# Top_Level.net
KiCad netlist of a schematic drawn in Altium Designer
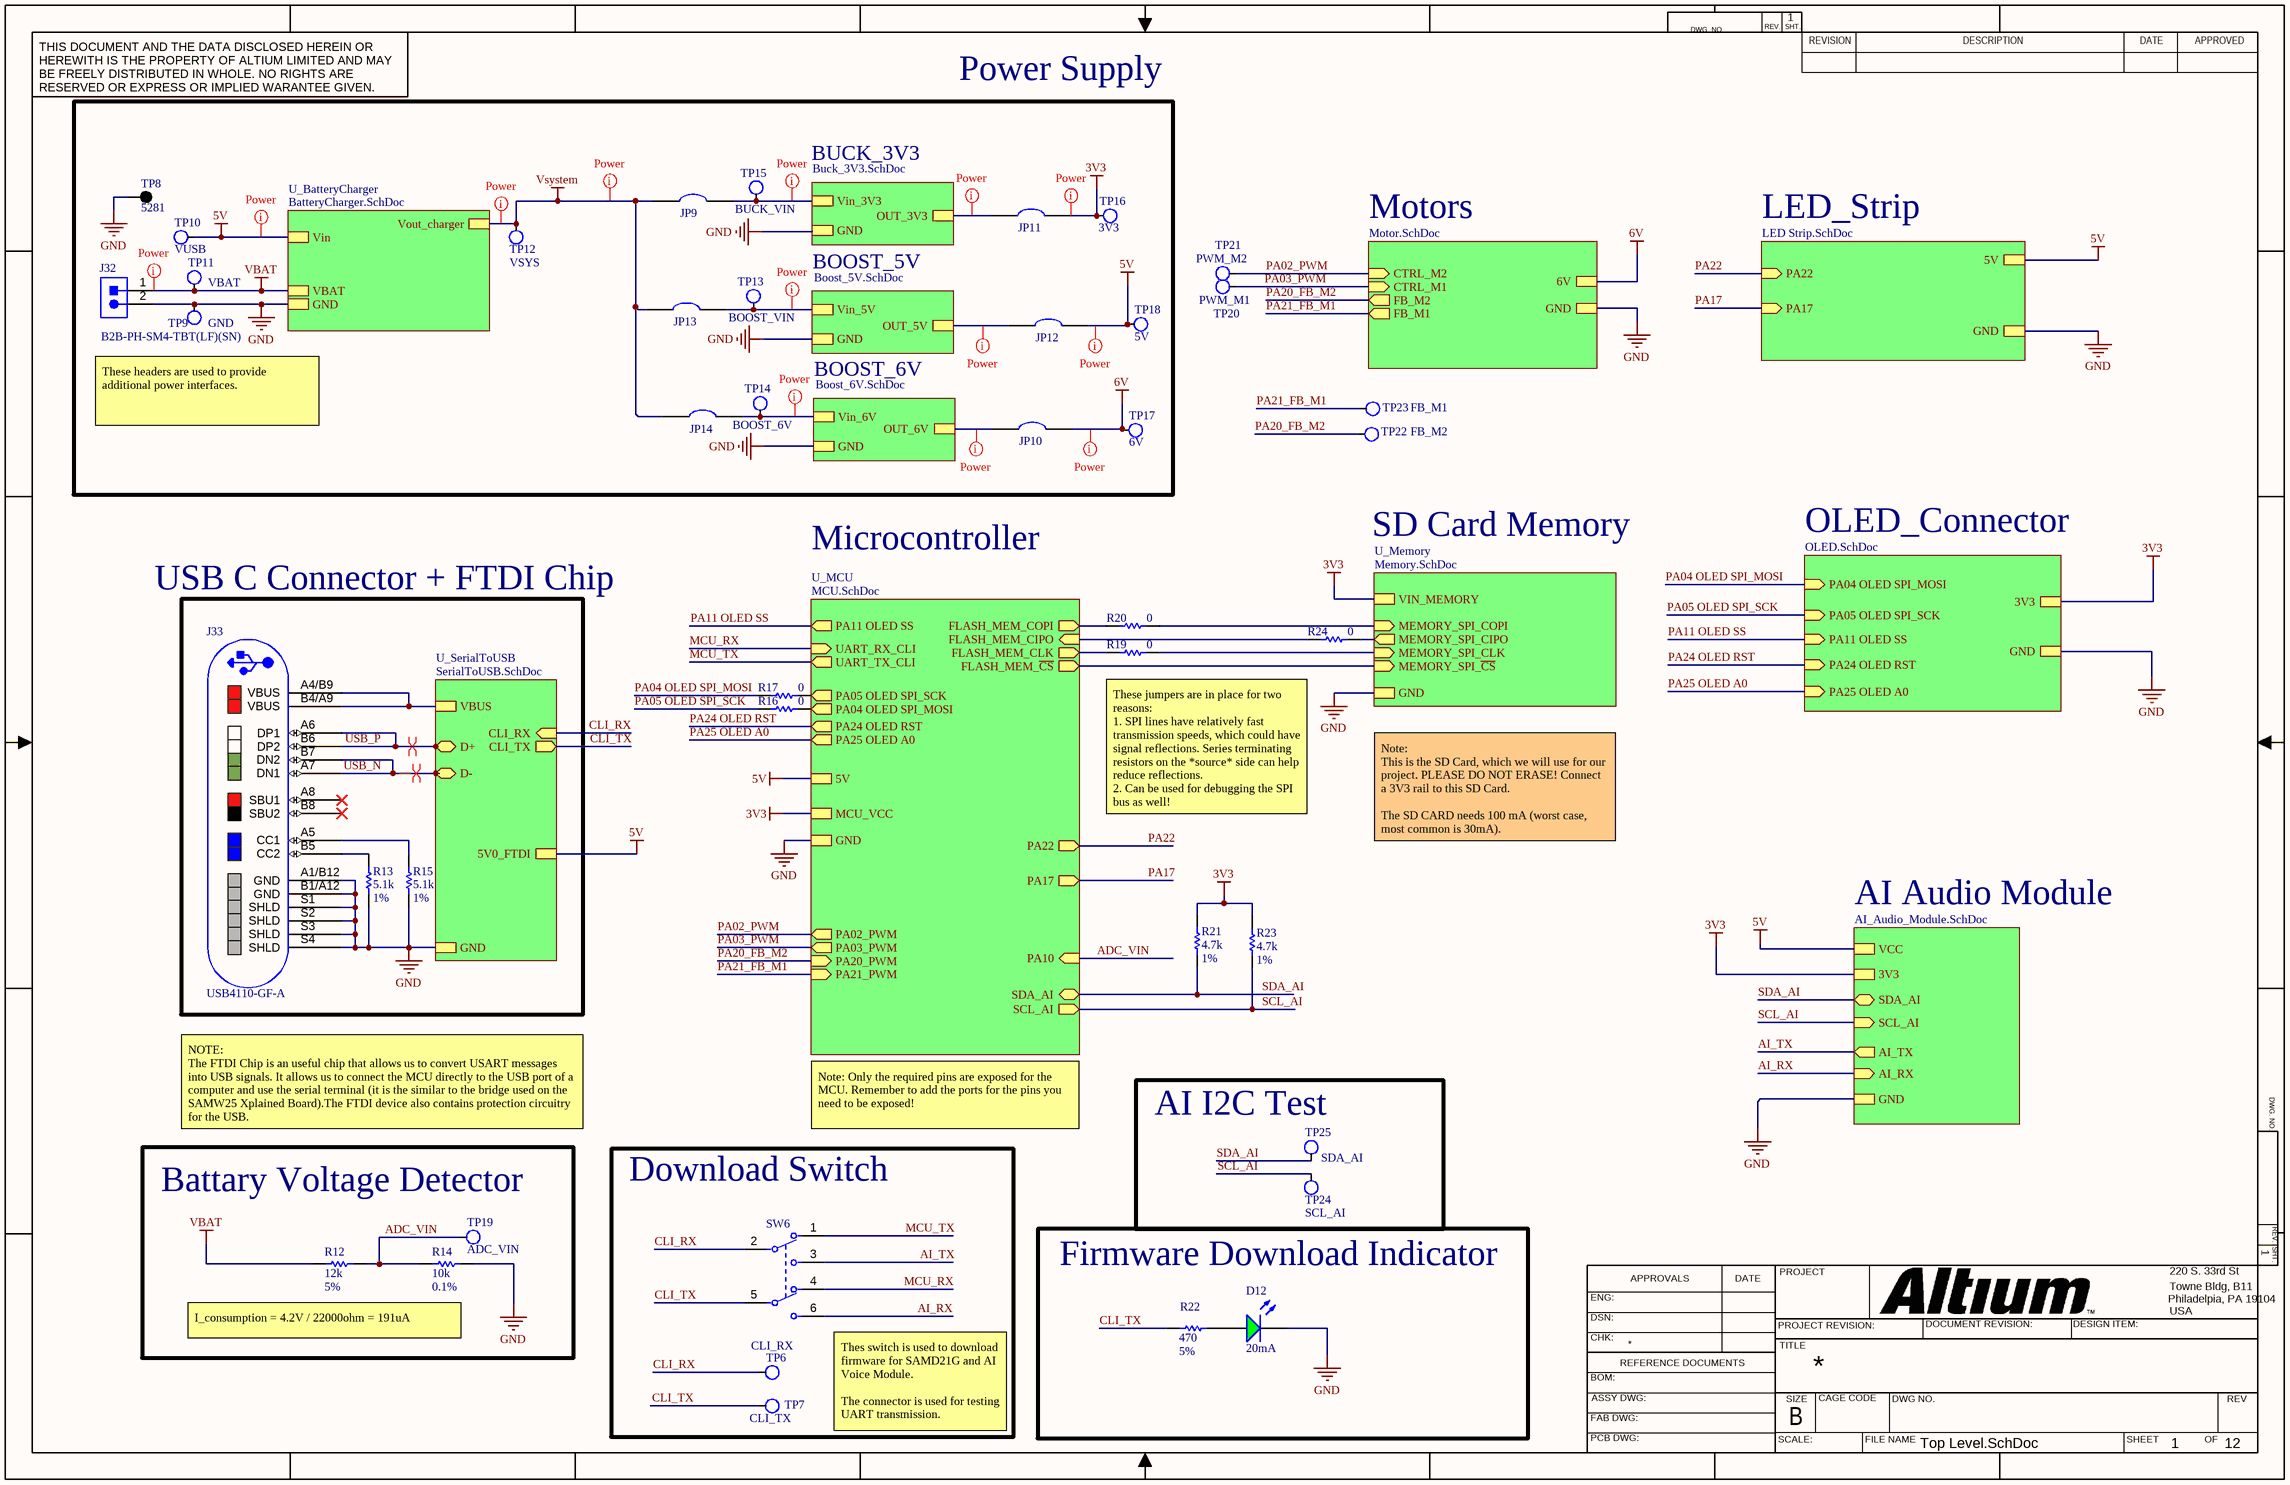
[diagram p0: Top Level.SchDoc]

(export (version "E")
  (design (tool "Eeschema 10.0.6"))
  (components
    (comp (ref "D12")
      (value "LSM0805452V")
      (footprint "LED_0805")
      (description "Single Color LED, Green, 0805")
      (fields (field (name "CURRENT") "20mA"))
      (libsource (lib "University of Pennsylvania (ESE)") (part "LED-GREEN-AK-2"))
    )
    (comp (ref "J32")
      (value "B2B-PH-SM4-TBT(LF)(SN)")
      (footprint "FP-B2B-PH-SM4-TBT_LF_SN-MFG")
      (libsource (lib "University of Pennsylvania (ESE)") (part "Header 1X2"))
    )
    (comp (ref "J33")
      (value "USB4110-GF-A")
      (footprint "FP-USB4110-GF-A-MFG")
      (libsource (lib "University of Pennsylvania (ESE)") (part "USB4110-GF-A"))
    )
    (comp (ref "JP9")
      (value "0603 link")
      (footprint "0603_JP_RES")
      (description "0O link, SMD, 0603, Solder Bridge Option")
      (fields (field (name "MANUFACTURER") "Generic") (field (name "SOURCE") "Shunts and Jumpers.SchLib"))
      (libsource (lib "University of Pennsylvania (ESE)") (part "CMP-ROOT-0007-1"))
    )
    (comp (ref "JP10")
      (value "0603 link")
      (footprint "0603_JP_RES")
      (description "0O link, SMD, 0603, Solder Bridge Option")
      (fields (field (name "MANUFACTURER") "Generic") (field (name "SOURCE") "Shunts and Jumpers.SchLib"))
      (libsource (lib "University of Pennsylvania (ESE)") (part "CMP-ROOT-0007-1"))
    )
    (comp (ref "JP11")
      (value "0603 link")
      (footprint "0603_JP_RES")
      (description "0O link, SMD, 0603, Solder Bridge Option")
      (fields (field (name "MANUFACTURER") "Generic") (field (name "SOURCE") "Shunts and Jumpers.SchLib"))
      (libsource (lib "University of Pennsylvania (ESE)") (part "CMP-ROOT-0007-1"))
    )
    (comp (ref "JP12")
      (value "0603 link")
      (footprint "0603_JP_RES")
      (description "0O link, SMD, 0603, Solder Bridge Option")
      (fields (field (name "MANUFACTURER") "Generic") (field (name "SOURCE") "Shunts and Jumpers.SchLib"))
      (libsource (lib "University of Pennsylvania (ESE)") (part "CMP-ROOT-0007-1"))
    )
    (comp (ref "JP13")
      (value "0603 link")
      (footprint "0603_JP_RES")
      (description "0O link, SMD, 0603, Solder Bridge Option")
      (fields (field (name "MANUFACTURER") "Generic") (field (name "SOURCE") "Shunts and Jumpers.SchLib"))
      (libsource (lib "University of Pennsylvania (ESE)") (part "CMP-ROOT-0007-1"))
    )
    (comp (ref "JP14")
      (value "0603 link")
      (footprint "0603_JP_RES")
      (description "0O link, SMD, 0603, Solder Bridge Option")
      (fields (field (name "MANUFACTURER") "Generic") (field (name "SOURCE") "Shunts and Jumpers.SchLib"))
      (libsource (lib "University of Pennsylvania (ESE)") (part "CMP-ROOT-0007-1"))
    )
    (comp (ref "R12")
      (value "12k")
      (footprint "0603_RES")
      (description "Resistor Surface Mount, 12K Ohms, 0603 Footprint, 5% Tolerance 0.1W")
      (fields
        (field (name "TOLERANCE") "5%")
        (field (name "MANUFACTURER") "Various")
        (field (name "Comment") "RES 0603 12K 5%")
      )
      (libsource (lib "University of Pennsylvania (ESE)") (part "res"))
    )
    (comp (ref "R13")
      (value "5.1k")
      (footprint "0603_RES")
      (description "Resistor Surface Mount, 5.1K Ohms, 0603 Footprint, 1% Tolerance 0.1W")
      (fields
        (field (name "TOLERANCE") "1%")
        (field (name "MANUFACTURER") "Various")
        (field (name "Comment") "RES 0603 5.1K 1%")
      )
      (libsource (lib "University of Pennsylvania (ESE)") (part "res"))
    )
    (comp (ref "R14")
      (value "10k")
      (footprint "0603_RES")
      (description "Resistor Surface Mount, 10K Ohms, 0603 Footprint, 0.1% Tolerance 0.1W")
      (fields
        (field (name "TOLERANCE") "0.1%")
        (field (name "MANUFACTURER") "Various")
        (field (name "Comment") "RES 0603 10K 0.1%")
      )
      (libsource (lib "University of Pennsylvania (ESE)") (part "res"))
    )
    (comp (ref "R15")
      (value "5.1k")
      (footprint "0603_RES")
      (description "Resistor Surface Mount, 5.1K Ohms, 0603 Footprint, 1% Tolerance 0.1W")
      (fields
        (field (name "TOLERANCE") "1%")
        (field (name "MANUFACTURER") "Various")
        (field (name "Comment") "RES 0603 5.1K 1%")
      )
      (libsource (lib "University of Pennsylvania (ESE)") (part "res"))
    )
    (comp (ref "R16")
      (value "0")
      (footprint "0603_RES")
      (description "Resistor Surface Mount, 0 Ohms, 0603 Footprint, 5% Tolerance 0.1W")
      (fields (field (name "TOLERANCE") "5%") (field (name "JLCPCB PART #") "C21189"))
      (libsource (lib "University of Pennsylvania (ESE)") (part "res"))
    )
    (comp (ref "R17")
      (value "0")
      (footprint "0603_RES")
      (description "Resistor Surface Mount, 0 Ohms, 0603 Footprint, 5% Tolerance 0.1W")
      (fields (field (name "TOLERANCE") "5%") (field (name "JLCPCB PART #") "C21189"))
      (libsource (lib "University of Pennsylvania (ESE)") (part "res"))
    )
    (comp (ref "R19")
      (value "0")
      (footprint "0603_RES")
      (description "Resistor Surface Mount, 0 Ohms, 0603 Footprint, 5% Tolerance 0.1W")
      (fields (field (name "TOLERANCE") "5%") (field (name "JLCPCB PART #") "C21189"))
      (libsource (lib "University of Pennsylvania (ESE)") (part "res"))
    )
    (comp (ref "R20")
      (value "0")
      (footprint "0603_RES")
      (description "Resistor Surface Mount, 0 Ohms, 0603 Footprint, 5% Tolerance 0.1W")
      (fields (field (name "TOLERANCE") "5%") (field (name "JLCPCB PART #") "C21189"))
      (libsource (lib "University of Pennsylvania (ESE)") (part "res"))
    )
    (comp (ref "R21")
      (value "4.7k")
      (footprint "0603_RES")
      (description "Resistor Surface Mount, 4.7K Ohms, 0603 Footprint, 1% Tolerance 0.1W")
      (fields
        (field (name "TOLERANCE") "1%")
        (field (name "MANUFACTURER") "Various")
        (field (name "Comment") "RES 0603 4.7K 1%")
      )
      (libsource (lib "University of Pennsylvania (ESE)") (part "res"))
    )
    (comp (ref "R22")
      (value "470")
      (footprint "0805_RES")
      (description "Resistor Surface Mount, 470 Ohms, 0805 Footprint, 5% Tolerance 0.125W")
      (fields
        (field (name "TOLERANCE") "5%")
        (field (name "MANUFACTURER") "Various")
        (field (name "Comment") "RES 0805 470 5%")
      )
      (libsource (lib "University of Pennsylvania (ESE)") (part "res"))
    )
    (comp (ref "R23")
      (value "4.7k")
      (footprint "0603_RES")
      (description "Resistor Surface Mount, 4.7K Ohms, 0603 Footprint, 1% Tolerance 0.1W")
      (fields
        (field (name "TOLERANCE") "1%")
        (field (name "MANUFACTURER") "Various")
        (field (name "Comment") "RES 0603 4.7K 1%")
      )
      (libsource (lib "University of Pennsylvania (ESE)") (part "res"))
    )
    (comp (ref "R24")
      (value "0")
      (footprint "0603_RES")
      (description "Resistor Surface Mount, 0 Ohms, 0603 Footprint, 5% Tolerance 0.1W")
      (fields (field (name "TOLERANCE") "5%") (field (name "JLCPCB PART #") "C21189"))
      (libsource (lib "University of Pennsylvania (ESE)") (part "res"))
    )
    (comp (ref "SW6")
      (value "JS202011JCQN")
      (footprint "FP-JS202011JCQN-MFG")
      (description "Slide Switch, 2 Positions, DPDT, Latched, 0.3A, 6VDC, Solder Terminal, Surface Mount-straight")
      (libsource (lib "University of Pennsylvania (ESE)") (part "DPDT"))
    )
    (comp (ref "TP6")
      (value "Testpad")
      (footprint "Keystone 5000 Series")
      (description "Test Pad/Point (Testpoint, Testpad), for probing")
      (fields (field (name "NETNAME") "CLI_RX"))
      (libsource (lib "University of Pennsylvania (ESE)") (part "Test Pad"))
    )
    (comp (ref "TP7")
      (value "Testpad")
      (footprint "Keystone 5000 Series")
      (description "Test Pad/Point (Testpoint, Testpad), for probing")
      (fields (field (name "NETNAME") "CLI_TX"))
      (libsource (lib "University of Pennsylvania (ESE)") (part "Test Pad"))
    )
    (comp (ref "TP8")
      (value "5281")
      (footprint "KSTN-5011_V")
      (description "Circuit Board Hardware - PCB TEST POINT BLACK MULTIPURPOSE 5011 5281")
      (libsource (lib "University of Pennsylvania (ESE)") (part "TESTPOINT_BLACK"))
    )
    (comp (ref "TP9")
      (value "Testpad")
      (footprint "Testpad-HeaderPin")
      (description "Test Pad/Point (Testpoint, Testpad), for probing")
      (fields (field (name "NETNAME") "GND"))
      (libsource (lib "University of Pennsylvania (ESE)") (part "Test Pad"))
    )
    (comp (ref "TP10")
      (value "Testpad")
      (footprint "Keystone 5000 Series")
      (description "Test Pad/Point (Testpoint, Testpad), for probing")
      (fields (field (name "NETNAME") "VUSB"))
      (libsource (lib "University of Pennsylvania (ESE)") (part "Test Pad"))
    )
    (comp (ref "TP11")
      (value "Testpad")
      (footprint "Keystone 5000 Series")
      (description "Test Pad/Point (Testpoint, Testpad), for probing")
      (fields (field (name "NETNAME") "VBAT"))
      (libsource (lib "University of Pennsylvania (ESE)") (part "Test Pad"))
    )
    (comp (ref "TP12")
      (value "Testpad")
      (footprint "Keystone 5000 Series")
      (description "Test Pad/Point (Testpoint, Testpad), for probing")
      (fields (field (name "NETNAME") "VSYS"))
      (libsource (lib "University of Pennsylvania (ESE)") (part "Test Pad"))
    )
    (comp (ref "TP13")
      (value "Testpad")
      (footprint "Keystone 5000 Series")
      (description "Test Pad/Point (Testpoint, Testpad), for probing")
      (fields (field (name "NETNAME") "BOOST_VIN"))
      (libsource (lib "University of Pennsylvania (ESE)") (part "Test Pad"))
    )
    (comp (ref "TP14")
      (value "Testpad")
      (footprint "Keystone 5000 Series")
      (description "Test Pad/Point (Testpoint, Testpad), for probing")
      (fields (field (name "NETNAME") "BOOST_6V"))
      (libsource (lib "University of Pennsylvania (ESE)") (part "Test Pad"))
    )
    (comp (ref "TP15")
      (value "Testpad")
      (footprint "Keystone 5000 Series")
      (description "Test Pad/Point (Testpoint, Testpad), for probing")
      (fields (field (name "NETNAME") "BUCK_VIN"))
      (libsource (lib "University of Pennsylvania (ESE)") (part "Test Pad"))
    )
    (comp (ref "TP16")
      (value "Testpad")
      (footprint "Keystone 5000 Series")
      (description "Test Pad/Point (Testpoint, Testpad), for probing")
      (fields (field (name "NETNAME") "3V3"))
      (libsource (lib "University of Pennsylvania (ESE)") (part "Test Pad"))
    )
    (comp (ref "TP17")
      (value "Testpad")
      (footprint "Keystone 5000 Series")
      (description "Test Pad/Point (Testpoint, Testpad), for probing")
      (fields (field (name "NETNAME") "6V"))
      (libsource (lib "University of Pennsylvania (ESE)") (part "Test Pad"))
    )
    (comp (ref "TP18")
      (value "Testpad")
      (footprint "Keystone 5000 Series")
      (description "Test Pad/Point (Testpoint, Testpad), for probing")
      (fields (field (name "NETNAME") "5V"))
      (libsource (lib "University of Pennsylvania (ESE)") (part "Test Pad"))
    )
    (comp (ref "TP19")
      (value "Testpad")
      (footprint "Keystone 5000 Series")
      (description "Test Pad/Point (Testpoint, Testpad), for probing")
      (fields (field (name "NETNAME") "ADC_VIN"))
      (libsource (lib "University of Pennsylvania (ESE)") (part "Test Pad"))
    )
    (comp (ref "TP20")
      (value "Testpad")
      (footprint "Keystone 5000 Series")
      (description "Test Pad/Point (Testpoint, Testpad), for probing")
      (fields (field (name "NETNAME") "PWM_M1"))
      (libsource (lib "University of Pennsylvania (ESE)") (part "Test Pad"))
    )
    (comp (ref "TP21")
      (value "Testpad")
      (footprint "Keystone 5000 Series")
      (description "Test Pad/Point (Testpoint, Testpad), for probing")
      (fields (field (name "NETNAME") "PWM_M2"))
      (libsource (lib "University of Pennsylvania (ESE)") (part "Test Pad"))
    )
    (comp (ref "TP22")
      (value "Testpad")
      (footprint "Keystone 5000 Series")
      (description "Test Pad/Point (Testpoint, Testpad), for probing")
      (fields (field (name "NETNAME") "FB_M2"))
      (libsource (lib "University of Pennsylvania (ESE)") (part "Test Pad"))
    )
    (comp (ref "TP23")
      (value "Testpad")
      (footprint "Keystone 5000 Series")
      (description "Test Pad/Point (Testpoint, Testpad), for probing")
      (fields (field (name "NETNAME") "FB_M1"))
      (libsource (lib "University of Pennsylvania (ESE)") (part "Test Pad"))
    )
    (comp (ref "TP24")
      (value "Testpad")
      (footprint "Keystone 5000 Series")
      (description "Test Pad/Point (Testpoint, Testpad), for probing")
      (fields (field (name "NETNAME") "SCL_AI"))
      (libsource (lib "University of Pennsylvania (ESE)") (part "Test Pad"))
    )
    (comp (ref "TP25")
      (value "Testpad")
      (footprint "Keystone 5000 Series")
      (description "Test Pad/Point (Testpoint, Testpad), for probing")
      (fields (field (name "NETNAME") "SDA_AI"))
      (libsource (lib "University of Pennsylvania (ESE)") (part "Test Pad"))
    )
  )
  (nets
    (net (code "2") (name "/ADC_VIN") (class "Default")
      (node (ref "R12") (pin "2") (pinfunction "2_2") (pintype "passive"))
      (node (ref "R14") (pin "1") (pinfunction "1_1") (pintype "passive"))
      (node (ref "TP19") (pin "1") (pinfunction "1_1") (pintype "passive"))
    )
    (net (code "3") (name "/AI_RX") (class "Default")
      (node (ref "SW6") (pin "6") (pinfunction "6_6") (pintype "passive"))
    )
    (net (code "4") (name "/AI_TX") (class "Default")
      (node (ref "SW6") (pin "3") (pinfunction "3_3") (pintype "passive"))
    )
    (net (code "5") (name "/CLI_RX") (class "Default")
      (node (ref "SW6") (pin "2") (pinfunction "2_2") (pintype "passive"))
      (node (ref "TP6") (pin "1") (pinfunction "1_1") (pintype "passive"))
    )
    (net (code "6") (name "/CLI_TX") (class "Default")
      (node (ref "R22") (pin "1") (pinfunction "1_1") (pintype "passive"))
      (node (ref "SW6") (pin "5") (pinfunction "5_5") (pintype "passive"))
      (node (ref "TP7") (pin "1") (pinfunction "1_1") (pintype "passive"))
    )
    (net (code "7") (name "/FLASH_MEM_CIPO") (class "Default")
      (node (ref "R24") (pin "1") (pinfunction "1_1") (pintype "passive"))
    )
    (net (code "8") (name "/FLASH_MEM_CLK") (class "Default")
      (node (ref "R19") (pin "1") (pinfunction "1_1") (pintype "passive"))
    )
    (net (code "9") (name "/FLASH_MEM_COPI") (class "Default")
      (node (ref "R20") (pin "1") (pinfunction "1_1") (pintype "passive"))
    )
    (net (code "11") (name "/MCU_RX") (class "Default")
      (node (ref "SW6") (pin "4") (pinfunction "4_4") (pintype "passive"))
    )
    (net (code "12") (name "/MCU_TX") (class "Default")
      (node (ref "SW6") (pin "1") (pinfunction "1_1") (pintype "passive"))
    )
    (net (code "13") (name "/MEMORY_SPI_CIPO") (class "Default")
      (node (ref "R24") (pin "2") (pinfunction "2_2") (pintype "passive"))
    )
    (net (code "14") (name "/MEMORY_SPI_CLK") (class "Default")
      (node (ref "R19") (pin "2") (pinfunction "2_2") (pintype "passive"))
    )
    (net (code "15") (name "/MEMORY_SPI_COPI") (class "Default")
      (node (ref "R20") (pin "2") (pinfunction "2_2") (pintype "passive"))
    )
    (net (code "16") (name "/OUT_3V3") (class "Default")
      (node (ref "JP11") (pin "1") (pinfunction "1_1") (pintype "passive"))
    )
    (net (code "17") (name "/OUT_5V") (class "Default")
      (node (ref "JP12") (pin "1") (pinfunction "1_1") (pintype "passive"))
    )
    (net (code "18") (name "/OUT_6V") (class "Default")
      (node (ref "JP10") (pin "1") (pinfunction "1_1") (pintype "passive"))
    )
    (net (code "19") (name "/PA02_PWM") (class "Default")
      (node (ref "TP21") (pin "1") (pinfunction "1_1") (pintype "passive"))
    )
    (net (code "20") (name "/PA03_PWM") (class "Default")
      (node (ref "TP20") (pin "1") (pinfunction "1_1") (pintype "passive"))
    )
    (net (code "21") (name "/PA04 OLED SPI_MOSI") (class "Default")
      (node (ref "R17") (pin "1") (pinfunction "1_1") (pintype "passive"))
    )
    (net (code "22") (name "/PA04 OLED SPI_MOSI_1") (class "Default")
      (node (ref "R16") (pin "2") (pinfunction "2_2") (pintype "passive"))
    )
    (net (code "23") (name "/PA05 OLED SPI_SCK") (class "Default")
      (node (ref "R16") (pin "1") (pinfunction "1_1") (pintype "passive"))
    )
    (net (code "24") (name "/PA05 OLED SPI_SCK_1") (class "Default")
      (node (ref "R17") (pin "2") (pinfunction "2_2") (pintype "passive"))
    )
    (net (code "27") (name "/PA20_FB_M2") (class "Default")
      (node (ref "TP22") (pin "1") (pinfunction "1_1") (pintype "passive"))
    )
    (net (code "28") (name "/PA21_FB_M1") (class "Default")
      (node (ref "TP23") (pin "1") (pinfunction "1_1") (pintype "passive"))
    )
    (net (code "31") (name "/SCL_AI") (class "Default")
      (node (ref "R23") (pin "1") (pinfunction "1_1") (pintype "passive"))
      (node (ref "TP24") (pin "1") (pinfunction "1_1") (pintype "passive"))
    )
    (net (code "32") (name "/SDA_AI") (class "Default")
      (node (ref "R21") (pin "1") (pinfunction "1_1") (pintype "passive"))
      (node (ref "TP25") (pin "1") (pinfunction "1_1") (pintype "passive"))
    )
    (net (code "33") (name "/USB_N") (class "Default")
      (node (ref "J33") (pin "A7") (pinfunction "DN1_A7") (pintype "bidirectional"))
      (node (ref "J33") (pin "B7") (pinfunction "DN2_B7") (pintype "bidirectional"))
    )
    (net (code "34") (name "/USB_P") (class "Default")
      (node (ref "J33") (pin "A6") (pinfunction "DP1_A6") (pintype "bidirectional"))
      (node (ref "J33") (pin "B6") (pinfunction "DP2_B6") (pintype "bidirectional"))
    )
    (net (code "35") (name "/VBUS") (class "Default")
      (node (ref "J33") (pin "A4/B9") (pinfunction "VBUS_A4/B9") (pintype "power_in"))
      (node (ref "J33") (pin "B4/A9") (pinfunction "VBUS_B4/A9") (pintype "power_in"))
    )
    (net (code "36") (name "/Vin_3V3") (class "Default")
      (node (ref "JP9") (pin "2") (pinfunction "2_2") (pintype "passive"))
      (node (ref "TP15") (pin "1") (pinfunction "1_1") (pintype "passive"))
    )
    (net (code "37") (name "/Vin_5V") (class "Default")
      (node (ref "JP13") (pin "2") (pinfunction "2_2") (pintype "passive"))
      (node (ref "TP13") (pin "1") (pinfunction "1_1") (pintype "passive"))
    )
    (net (code "38") (name "/Vin_6V") (class "Default")
      (node (ref "JP14") (pin "2") (pinfunction "2_2") (pintype "passive"))
      (node (ref "TP14") (pin "1") (pinfunction "1_1") (pintype "passive"))
    )
    (net (code "39") (name "3V3") (class "Default")
      (node (ref "JP11") (pin "2") (pinfunction "2_2") (pintype "passive"))
      (node (ref "R21") (pin "2") (pinfunction "2_2") (pintype "passive"))
      (node (ref "R23") (pin "2") (pinfunction "2_2") (pintype "passive"))
      (node (ref "TP16") (pin "1") (pinfunction "1_1") (pintype "passive"))
    )
    (net (code "40") (name "5V") (class "Default")
      (node (ref "JP12") (pin "2") (pinfunction "2_2") (pintype "passive"))
      (node (ref "TP10") (pin "1") (pinfunction "1_1") (pintype "passive"))
      (node (ref "TP18") (pin "1") (pinfunction "1_1") (pintype "passive"))
    )
    (net (code "41") (name "6V") (class "Default")
      (node (ref "JP10") (pin "2") (pinfunction "2_2") (pintype "passive"))
      (node (ref "TP17") (pin "1") (pinfunction "1_1") (pintype "passive"))
    )
    (net (code "42") (name "GND") (class "Default")
      (node (ref "D12") (pin "K") (pinfunction "K_K") (pintype "passive"))
      (node (ref "J32") (pin "2") (pinfunction "2_2") (pintype "passive"))
      (node (ref "J33") (pin "A1/B12") (pinfunction "GND_A1/B12") (pintype "power_in"))
      (node (ref "J33") (pin "B1/A12") (pinfunction "GND_B1/A12") (pintype "power_in"))
      (node (ref "J33") (pin "S1") (pinfunction "SHLD_S1") (pintype "power_in"))
      (node (ref "J33") (pin "S2") (pinfunction "SHLD_S2") (pintype "power_in"))
      (node (ref "J33") (pin "S3") (pinfunction "SHLD_S3") (pintype "power_in"))
      (node (ref "J33") (pin "S4") (pinfunction "SHLD_S4") (pintype "power_in"))
      (node (ref "R13") (pin "1") (pinfunction "1_1") (pintype "passive"))
      (node (ref "R14") (pin "2") (pinfunction "2_2") (pintype "passive"))
      (node (ref "R15") (pin "1") (pinfunction "1_1") (pintype "passive"))
      (node (ref "TP8") (pin "1") (pinfunction "1_1") (pintype "passive"))
      (node (ref "TP9") (pin "1") (pinfunction "1_1") (pintype "passive"))
    )
    (net (code "43") (name "Net-(D12-PadA)") (class "Default")
      (node (ref "D12") (pin "A") (pinfunction "A_A") (pintype "passive"))
      (node (ref "R22") (pin "2") (pinfunction "2_2") (pintype "passive"))
    )
    (net (code "44") (name "Net-(J33-CC1)") (class "Default")
      (node (ref "J33") (pin "A5") (pinfunction "CC1_A5") (pintype "bidirectional"))
      (node (ref "R15") (pin "2") (pinfunction "2_2") (pintype "passive"))
    )
    (net (code "45") (name "Net-(J33-CC2)") (class "Default")
      (node (ref "J33") (pin "B5") (pinfunction "CC2_B5") (pintype "bidirectional"))
      (node (ref "R13") (pin "2") (pinfunction "2_2") (pintype "passive"))
    )
    (net (code "46") (name "VBAT") (class "Default")
      (node (ref "J32") (pin "1") (pinfunction "1_1") (pintype "passive"))
      (node (ref "R12") (pin "1") (pinfunction "1_1") (pintype "passive"))
      (node (ref "TP11") (pin "1") (pinfunction "1_1") (pintype "passive"))
    )
    (net (code "47") (name "Vsystem") (class "Default")
      (node (ref "JP13") (pin "1") (pinfunction "1_1") (pintype "passive"))
      (node (ref "JP14") (pin "1") (pinfunction "1_1") (pintype "passive"))
      (node (ref "JP9") (pin "1") (pinfunction "1_1") (pintype "passive"))
      (node (ref "TP12") (pin "1") (pinfunction "1_1") (pintype "passive"))
    )
    (net (code "48") (name "unconnected-(J33-SBU1-PadA8)") (class "Default")
      (node (ref "J33") (pin "A8") (pinfunction "SBU1_A8") (pintype "bidirectional+no_connect"))
    )
    (net (code "49") (name "unconnected-(J33-SBU2-PadB8)") (class "Default")
      (node (ref "J33") (pin "B8") (pinfunction "SBU2_B8") (pintype "bidirectional+no_connect"))
    )
  )
)
